# FPGA_DDR3_IO.net
KiCad netlist of a schematic drawn in Altium Designer
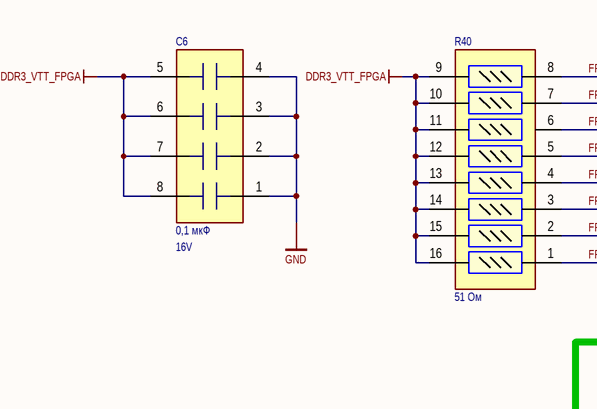
[diagram p0: FPGA_DDR3&IO.SchDoc, top left]
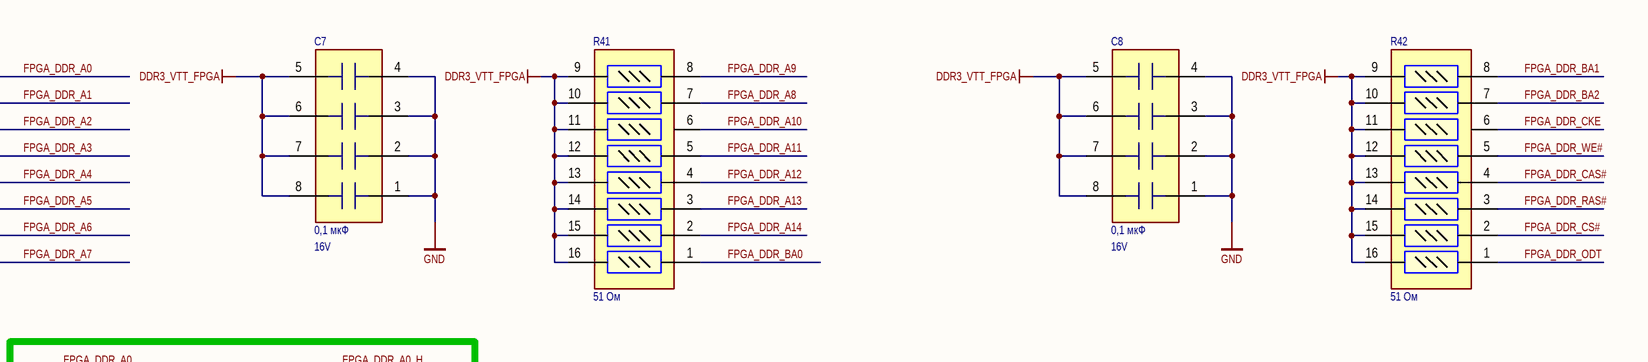
[diagram p1: FPGA_DDR3&IO.SchDoc, top right]
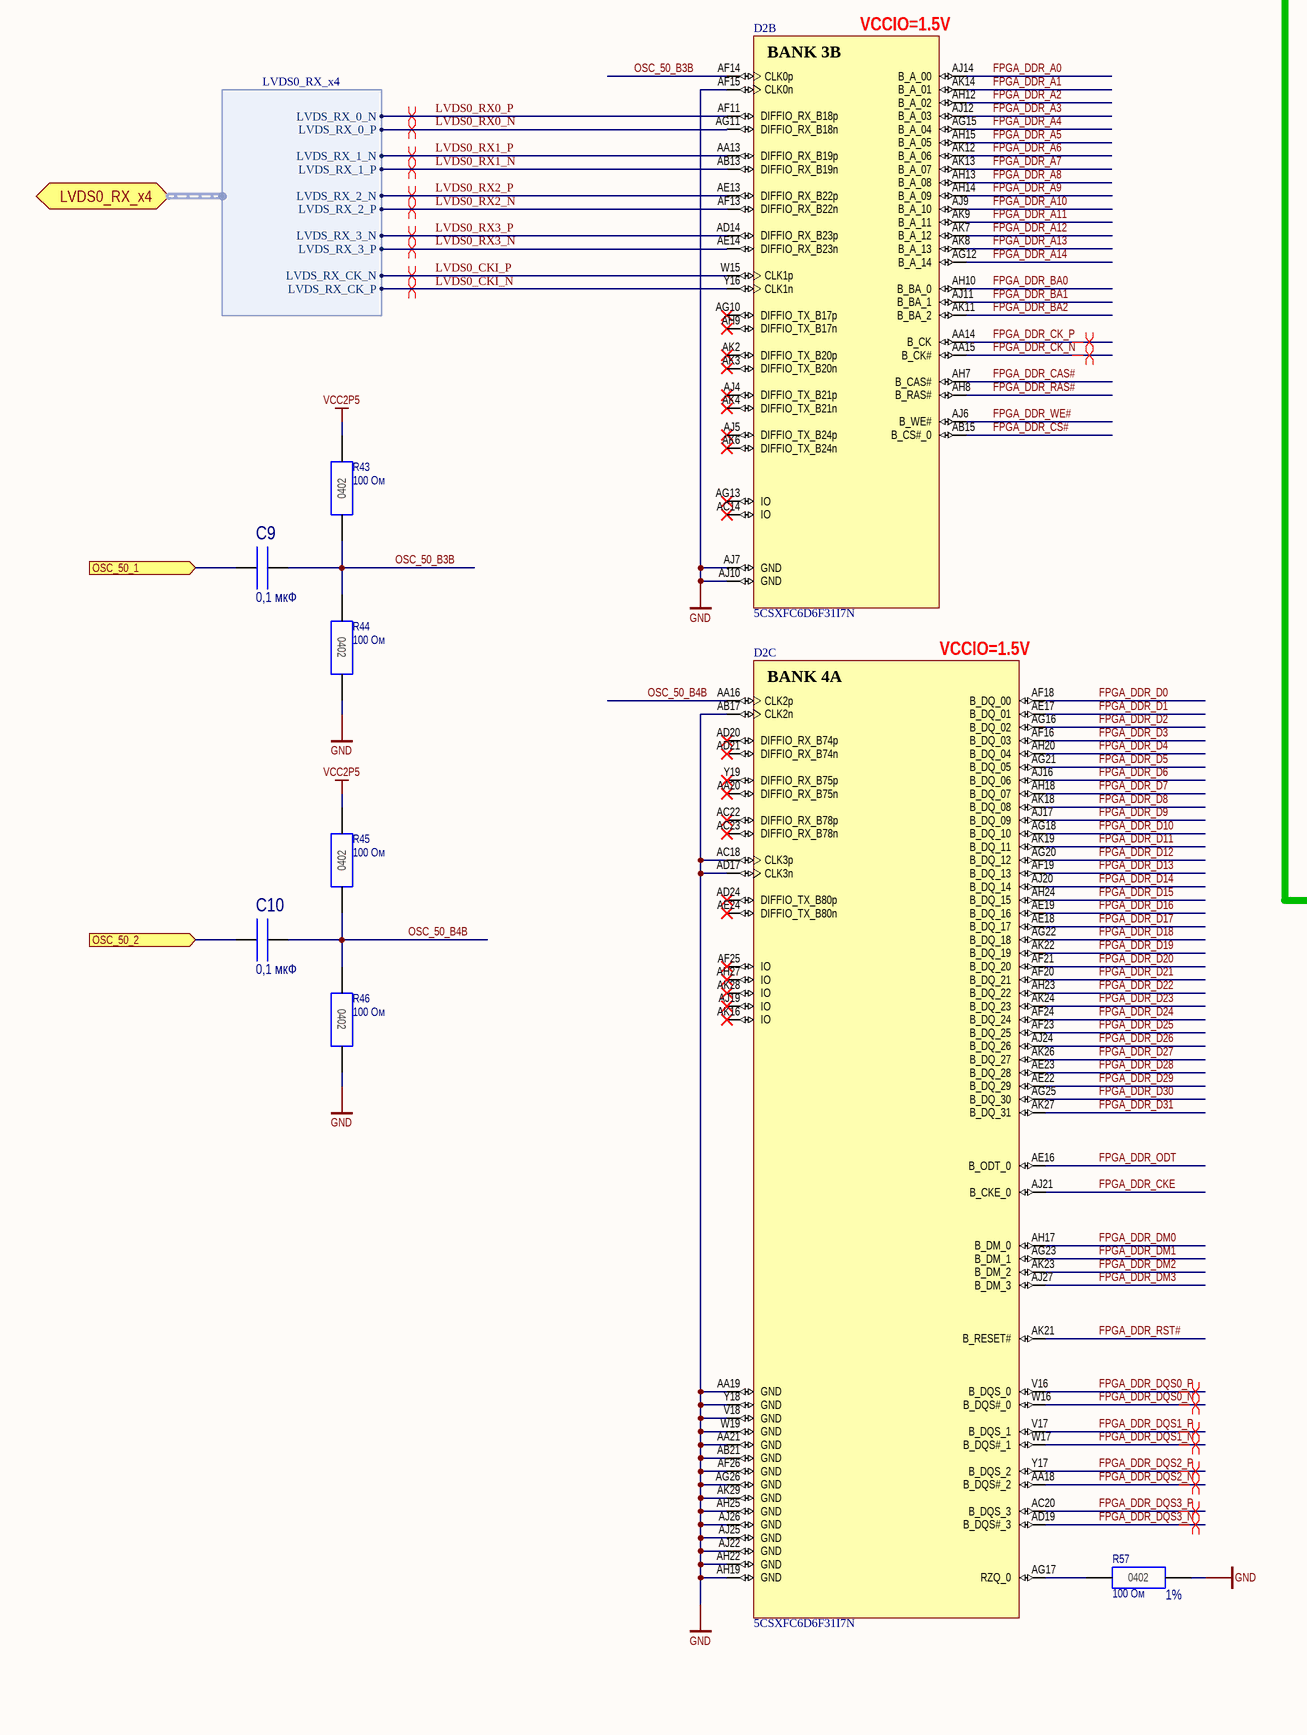
[diagram p2: FPGA_DDR3&IO.SchDoc, bottom left]
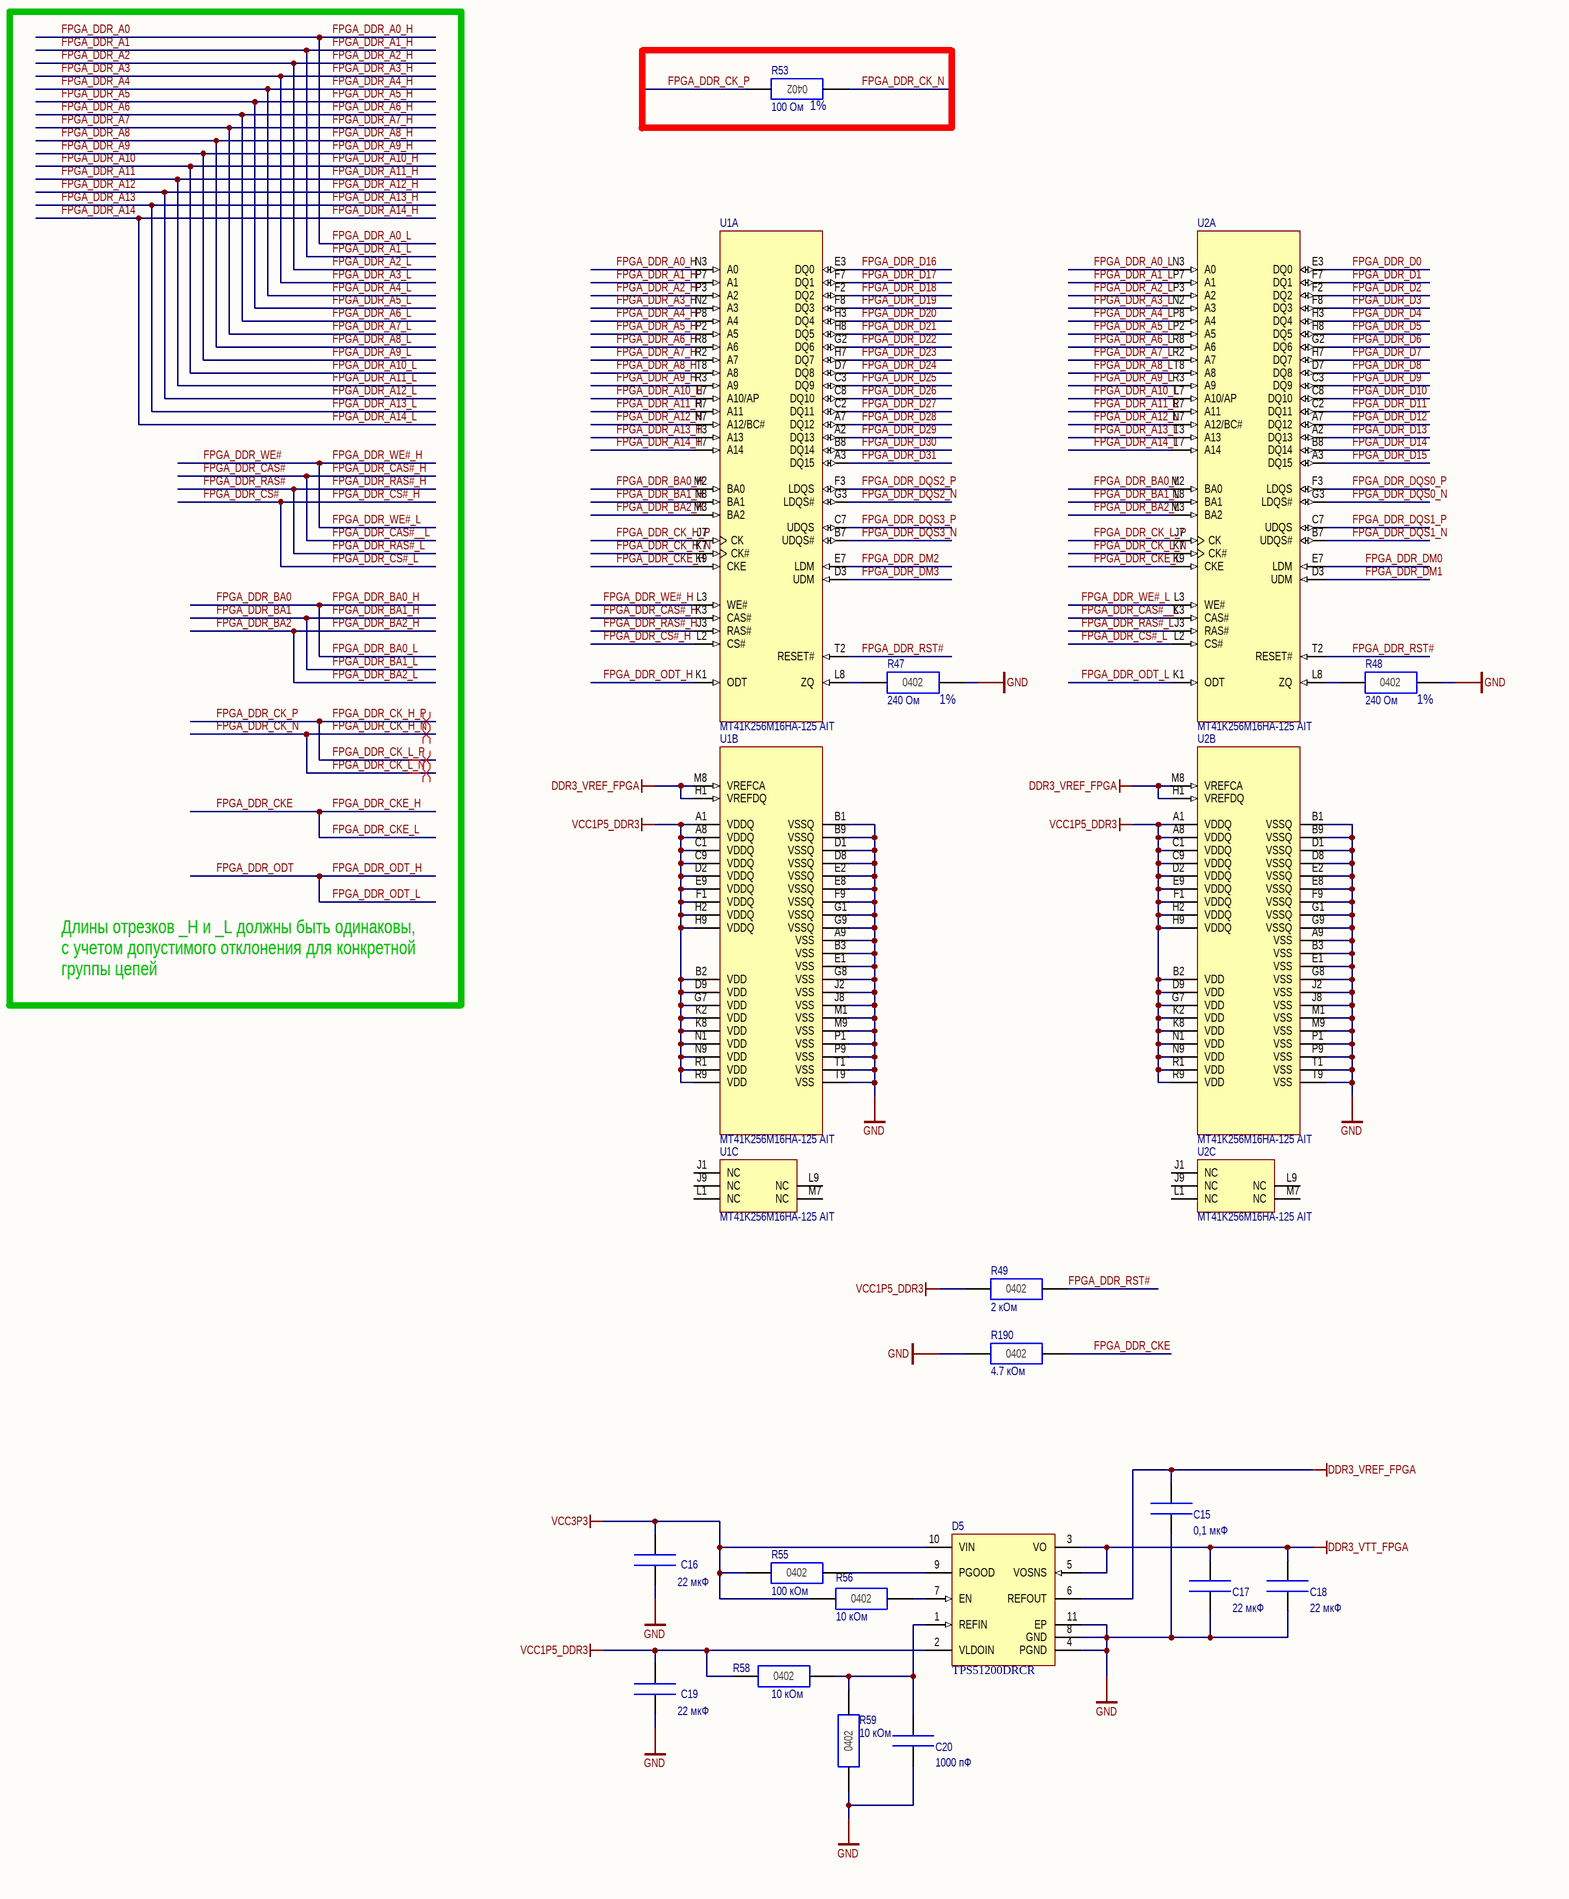
[diagram p3: FPGA_DDR3&IO.SchDoc, bottom right]

(export (version "E")
  (design (tool "Eeschema 10.0.6"))
  (components
    (comp (ref "C6")
      (value "0,1 мкФ")
      (footprint "CAF-80P319X159-8N")
      (description "Чип конденсатор керамический")
      (fields (field (name "V") "16V") (field (name "Comment") "W3A4YC104KAT2A"))
      (libsource (lib "SD_IC") (part "W3A4YC104KAT2A"))
    )
    (comp (ref "C7")
      (value "0,1 мкФ")
      (footprint "CAF-80P319X159-8N")
      (description "Чип конденсатор керамический")
      (fields (field (name "V") "16V") (field (name "Comment") "W3A4YC104KAT2A"))
      (libsource (lib "SD_IC") (part "W3A4YC104KAT2A"))
    )
    (comp (ref "C8")
      (value "0,1 мкФ")
      (footprint "CAF-80P319X159-8N")
      (description "Чип конденсатор керамический")
      (fields (field (name "V") "16V") (field (name "Comment") "W3A4YC104KAT2A"))
      (libsource (lib "SD_IC") (part "W3A4YC104KAT2A"))
    )
    (comp (ref "C9")
      (value "0,1 мкФ")
      (footprint "CC0402(1005)")
      (description "Чип конденсатор керамический")
      (fields (field (name "Comment") "CC0402-X7R-0,1 мкФ-20%-10В"))
      (libsource (lib "Чип конденсаторы") (part "CC0402-X7R-#-20%-10В"))
    )
    (comp (ref "C10")
      (value "0,1 мкФ")
      (footprint "CC0402(1005)")
      (description "Чип конденсатор керамический")
      (fields (field (name "Comment") "CC0402-X7R-0,1 мкФ-20%-10В"))
      (libsource (lib "Чип конденсаторы") (part "CC0402-X7R-#-20%-10В"))
    )
    (comp (ref "C15")
      (value "0,1 мкФ")
      (footprint "CC0402(1005)")
      (description "Чип конденсатор керамический")
      (fields (field (name "Comment") "CC0402-X7R-0,1 мкФ-20%-10В"))
      (libsource (lib "Чип конденсаторы") (part "CC0402-X7R-#-20%-10В"))
    )
    (comp (ref "C16")
      (value "22 мкФ")
      (footprint "CC0402(1005)")
      (description "Чип конденсатор керамический")
      (fields (field (name "Comment") "CC0402-X5R-22 мкФ-20%-6.3В"))
      (libsource (lib "Чип конденсаторы") (part "CC0402-X7R-#-20%-10В"))
    )
    (comp (ref "C17")
      (value "22 мкФ")
      (footprint "CC0402(1005)")
      (description "Чип конденсатор керамический")
      (fields (field (name "Comment") "CC0402-X5R-22 мкФ-20%-6.3В"))
      (libsource (lib "Чип конденсаторы") (part "CC0402-X7R-#-20%-10В"))
    )
    (comp (ref "C18")
      (value "22 мкФ")
      (footprint "CC0402(1005)")
      (description "Чип конденсатор керамический")
      (fields (field (name "Comment") "CC0402-X5R-22 мкФ-20%-6.3В"))
      (libsource (lib "Чип конденсаторы") (part "CC0402-X7R-#-20%-10В"))
    )
    (comp (ref "C19")
      (value "22 мкФ")
      (footprint "CC0402(1005)")
      (description "Чип конденсатор керамический")
      (fields (field (name "Comment") "CC0402-X5R-22 мкФ-20%-6.3В"))
      (libsource (lib "Чип конденсаторы") (part "CC0402-X7R-#-20%-10В"))
    )
    (comp (ref "C20")
      (value "1000 пФ")
      (footprint "CC0402(1005)")
      (description "Чип конденсатор керамический")
      (fields (field (name "Comment") "CC0402-NP01000 пФ-1%-50В"))
      (libsource (lib "Чип конденсаторы") (part "CC0402-X7R-#-20%-10В"))
    )
    (comp (ref "D2")
      (value "5CSXFC6D6F31I7N")
      (footprint "ALTR-FBGA896_A-200")
      (fields (field (name "MANUFACTURER") "Altera"))
      (libsource (lib "Altera Cyclone V_sd") (part "5CSXFC6D6F31I7N"))
    )
    (comp (ref "D5")
      (value "TPS51200DRCR")
      (footprint "TI-DRC10-2400X1650TP_V")
      (fields (field (name "MANUFACTURER") "Texas Instruments"))
      (libsource (lib "SD_IC") (part "TPS51200DRCR"))
    )
    (comp (ref "R40")
      (value "51 Ом")
      (footprint "CAT16-J8")
      (description "Набор чип резисторов")
      (fields (field (name "Comment") "YC248-JR-07-51 Ом"))
      (libsource (lib "SD_IC") (part "YC248-JR-07-#"))
    )
    (comp (ref "R41")
      (value "51 Ом")
      (footprint "CAT16-J8")
      (description "Набор чип резисторов")
      (fields (field (name "Comment") "YC248-JR-07-51 Ом"))
      (libsource (lib "SD_IC") (part "YC248-JR-07-#"))
    )
    (comp (ref "R42")
      (value "51 Ом")
      (footprint "CAT16-J8")
      (description "Набор чип резисторов")
      (fields (field (name "Comment") "YC248-JR-07-51 Ом"))
      (libsource (lib "SD_IC") (part "YC248-JR-07-#"))
    )
    (comp (ref "R43")
      (value "100 Ом")
      (footprint "CR0402(1005)")
      (description "Чип резистор")
      (fields (field (name "TOLERANCE") "5%") (field (name "Comment") "CR0402-100 Ом-±5%"))
      (libsource (lib "Резисторы") (part "CR0402-#-±5%"))
    )
    (comp (ref "R44")
      (value "100 Ом")
      (footprint "CR0402(1005)")
      (description "Чип резистор")
      (fields (field (name "TOLERANCE") "5%") (field (name "Comment") "CR0402-100 Ом-±5%"))
      (libsource (lib "") (part "CR0402-#-±5%_2"))
    )
    (comp (ref "R45")
      (value "100 Ом")
      (footprint "CR0402(1005)")
      (description "Чип резистор")
      (fields (field (name "TOLERANCE") "5%") (field (name "Comment") "CR0402-100 Ом-±5%"))
      (libsource (lib "Резисторы") (part "CR0402-#-±5%"))
    )
    (comp (ref "R46")
      (value "100 Ом")
      (footprint "CR0402(1005)")
      (description "Чип резистор")
      (fields (field (name "TOLERANCE") "5%") (field (name "Comment") "CR0402-100 Ом-±5%"))
      (libsource (lib "") (part "CR0402-#-±5%_2"))
    )
    (comp (ref "R47")
      (value "240 Ом")
      (footprint "CR0402(1005)")
      (description "Чип резистор")
      (fields (field (name "TOLERANCE") "1%") (field (name "Comment") "CR0402-240 Ом-±TOLERANCE"))
      (libsource (lib "") (part "CR0402-#-±5%_1"))
    )
    (comp (ref "R48")
      (value "240 Ом")
      (footprint "CR0402(1005)")
      (description "Чип резистор")
      (fields (field (name "TOLERANCE") "1%") (field (name "Comment") "CR0402-240 Ом-±TOLERANCE"))
      (libsource (lib "") (part "CR0402-#-±5%_1"))
    )
    (comp (ref "R49")
      (value "2 кОм")
      (footprint "CR0402(1005)")
      (description "Чип резистор")
      (fields (field (name "TOLERANCE") "5%") (field (name "Comment") "CR0402-2 кОм-±5%"))
      (libsource (lib "") (part "CR0402-#-±5%_1"))
    )
    (comp (ref "R53")
      (value "100 Ом")
      (footprint "CR0402(1005)")
      (description "Чип резистор")
      (fields (field (name "TOLERANCE") "1%") (field (name "Comment") "CR0402-100 Ом-±TOLERANCE"))
      (libsource (lib "") (part "CR0402-#-±5%_3"))
    )
    (comp (ref "R55")
      (value "100 кОм")
      (footprint "CR0402(1005)")
      (description "Чип резистор")
      (fields (field (name "TOLERANCE") "5%") (field (name "Comment") "CR0402-100 кОм-±5%"))
      (libsource (lib "") (part "CR0402-#-±5%_1"))
    )
    (comp (ref "R56")
      (value "10 кОм")
      (footprint "CR0402(1005)")
      (description "Чип резистор")
      (fields (field (name "TOLERANCE") "5%") (field (name "Comment") "CR0402-10 кОм-±5%"))
      (libsource (lib "") (part "CR0402-#-±5%_1"))
    )
    (comp (ref "R57")
      (value "100 Ом")
      (footprint "CR0402(1005)")
      (description "Чип резистор")
      (fields (field (name "TOLERANCE") "1%") (field (name "Comment") "CR0402-100 Ом-±TOLERANCE"))
      (libsource (lib "") (part "CR0402-#-±5%_1"))
    )
    (comp (ref "R58")
      (value "10 кОм")
      (footprint "CR0402(1005)")
      (description "Чип резистор")
      (fields (field (name "TOLERANCE") "5%") (field (name "Comment") "CR0402-10 кОм-±5%"))
      (libsource (lib "") (part "CR0402-#-±5%_1"))
    )
    (comp (ref "R59")
      (value "10 кОм")
      (footprint "CR0402(1005)")
      (description "Чип резистор")
      (fields (field (name "TOLERANCE") "5%") (field (name "Comment") "CR0402-10 кОм-±5%"))
      (libsource (lib "Резисторы") (part "CR0402-#-±5%"))
    )
    (comp (ref "R190")
      (value "4.7 кОм")
      (footprint "CR0402(1005)")
      (description "Чип резистор")
      (fields (field (name "TOLERANCE") "5%") (field (name "Comment") "CR0402-4.7 кОм-±5%"))
      (libsource (lib "") (part "CR0402-#-±5%_1"))
    )
    (comp (ref "U1")
      (value "MT41K256M16HA-125 AIT")
      (footprint "MICT-HA-96")
      (description "4Gb DDR3-1600 SDRAM, 256Mb x 16, 1.25ns, 1.35V, -40 to 95 degC, 96-Ball FBGA, Pb-Free")
      (fields (field (name "VOLTAGE") "1.35V ") (field (name "MANUFACTURER") "Micron"))
      (libsource (lib "SD_IC") (part "MT41K256M16HA-125 AIT"))
    )
    (comp (ref "U2")
      (value "MT41K256M16HA-125 AIT")
      (footprint "MICT-HA-96")
      (description "4Gb DDR3-1600 SDRAM, 256Mb x 16, 1.25ns, 1.35V, -40 to 95 degC, 96-Ball FBGA, Pb-Free")
      (fields (field (name "VOLTAGE") "1.35V ") (field (name "MANUFACTURER") "Micron"))
      (libsource (lib "SD_IC") (part "MT41K256M16HA-125 AIT"))
    )
  )
  (nets
    (net (code "2") (name "/FPGA_DDR_A0") (class "Default")
      (node (ref "D2") (pin "AJ14") (pinfunction "B_A_00_AJ14") (pintype "bidirectional"))
      (node (ref "R40") (pin "8") (pintype "passive"))
      (node (ref "U1") (pin "N3") (pinfunction "A0_N3") (pintype "input"))
      (node (ref "U2") (pin "N3") (pinfunction "A0_N3") (pintype "input"))
    )
    (net (code "3") (name "/FPGA_DDR_A1") (class "Default")
      (node (ref "D2") (pin "AK14") (pinfunction "B_A_01_AK14") (pintype "bidirectional"))
      (node (ref "R40") (pin "7") (pintype "passive"))
      (node (ref "U1") (pin "P7") (pinfunction "A1_P7") (pintype "input"))
      (node (ref "U2") (pin "P7") (pinfunction "A1_P7") (pintype "input"))
    )
    (net (code "4") (name "/FPGA_DDR_A2") (class "Default")
      (node (ref "D2") (pin "AH12") (pinfunction "B_A_02_AH12") (pintype "bidirectional"))
      (node (ref "R40") (pin "6") (pintype "passive"))
      (node (ref "U1") (pin "P3") (pinfunction "A2_P3") (pintype "input"))
      (node (ref "U2") (pin "P3") (pinfunction "A2_P3") (pintype "input"))
    )
    (net (code "5") (name "/FPGA_DDR_A3") (class "Default")
      (node (ref "D2") (pin "AJ12") (pinfunction "B_A_03_AJ12") (pintype "bidirectional"))
      (node (ref "R40") (pin "5") (pintype "passive"))
      (node (ref "U1") (pin "N2") (pinfunction "A3_N2") (pintype "input"))
      (node (ref "U2") (pin "N2") (pinfunction "A3_N2") (pintype "input"))
    )
    (net (code "6") (name "/FPGA_DDR_A4") (class "Default")
      (node (ref "D2") (pin "AG15") (pinfunction "B_A_04_AG15") (pintype "bidirectional"))
      (node (ref "R40") (pin "4") (pintype "passive"))
      (node (ref "U1") (pin "P8") (pinfunction "A4_P8") (pintype "input"))
      (node (ref "U2") (pin "P8") (pinfunction "A4_P8") (pintype "input"))
    )
    (net (code "7") (name "/FPGA_DDR_A5") (class "Default")
      (node (ref "D2") (pin "AH15") (pinfunction "B_A_05_AH15") (pintype "bidirectional"))
      (node (ref "R40") (pin "3") (pintype "passive"))
      (node (ref "U1") (pin "P2") (pinfunction "A5_P2") (pintype "input"))
      (node (ref "U2") (pin "P2") (pinfunction "A5_P2") (pintype "input"))
    )
    (net (code "8") (name "/FPGA_DDR_A6") (class "Default")
      (node (ref "D2") (pin "AK12") (pinfunction "B_A_06_AK12") (pintype "bidirectional"))
      (node (ref "R40") (pin "2") (pintype "passive"))
      (node (ref "U1") (pin "R8") (pinfunction "A6_R8") (pintype "input"))
      (node (ref "U2") (pin "R8") (pinfunction "A6_R8") (pintype "input"))
    )
    (net (code "9") (name "/FPGA_DDR_A7") (class "Default")
      (node (ref "D2") (pin "AK13") (pinfunction "B_A_07_AK13") (pintype "bidirectional"))
      (node (ref "R40") (pin "1") (pintype "passive"))
      (node (ref "U1") (pin "R2") (pinfunction "A7_R2") (pintype "input"))
      (node (ref "U2") (pin "R2") (pinfunction "A7_R2") (pintype "input"))
    )
    (net (code "10") (name "/FPGA_DDR_A8") (class "Default")
      (node (ref "D2") (pin "AH13") (pinfunction "B_A_08_AH13") (pintype "bidirectional"))
      (node (ref "R41") (pin "7") (pintype "passive"))
      (node (ref "U1") (pin "T8") (pinfunction "A8_T8") (pintype "input"))
      (node (ref "U2") (pin "T8") (pinfunction "A8_T8") (pintype "input"))
    )
    (net (code "11") (name "/FPGA_DDR_A9") (class "Default")
      (node (ref "D2") (pin "AH14") (pinfunction "B_A_09_AH14") (pintype "bidirectional"))
      (node (ref "R41") (pin "8") (pintype "passive"))
      (node (ref "U1") (pin "R3") (pinfunction "A9_R3") (pintype "input"))
      (node (ref "U2") (pin "R3") (pinfunction "A9_R3") (pintype "input"))
    )
    (net (code "12") (name "/FPGA_DDR_A10") (class "Default")
      (node (ref "D2") (pin "AJ9") (pinfunction "B_A_10_AJ9") (pintype "bidirectional"))
      (node (ref "R41") (pin "6") (pintype "passive"))
      (node (ref "U1") (pin "L7") (pinfunction "A10/AP_L7") (pintype "input"))
      (node (ref "U2") (pin "L7") (pinfunction "A10/AP_L7") (pintype "input"))
    )
    (net (code "13") (name "/FPGA_DDR_A11") (class "Default")
      (node (ref "D2") (pin "AK9") (pinfunction "B_A_11_AK9") (pintype "bidirectional"))
      (node (ref "R41") (pin "5") (pintype "passive"))
      (node (ref "U1") (pin "R7") (pinfunction "A11_R7") (pintype "input"))
      (node (ref "U2") (pin "R7") (pinfunction "A11_R7") (pintype "input"))
    )
    (net (code "14") (name "/FPGA_DDR_A12") (class "Default")
      (node (ref "D2") (pin "AK7") (pinfunction "B_A_12_AK7") (pintype "bidirectional"))
      (node (ref "R41") (pin "4") (pintype "passive"))
      (node (ref "U1") (pin "N7") (pinfunction "A12/BC#_N7") (pintype "input"))
      (node (ref "U2") (pin "N7") (pinfunction "A12/BC#_N7") (pintype "input"))
    )
    (net (code "15") (name "/FPGA_DDR_A13") (class "Default")
      (node (ref "D2") (pin "AK8") (pinfunction "B_A_13_AK8") (pintype "bidirectional"))
      (node (ref "R41") (pin "3") (pintype "passive"))
      (node (ref "U1") (pin "T3") (pinfunction "A13_T3") (pintype "input"))
      (node (ref "U2") (pin "T3") (pinfunction "A13_T3") (pintype "input"))
    )
    (net (code "16") (name "/FPGA_DDR_A14") (class "Default")
      (node (ref "D2") (pin "AG12") (pinfunction "B_A_14_AG12") (pintype "bidirectional"))
      (node (ref "R41") (pin "2") (pintype "passive"))
      (node (ref "U1") (pin "T7") (pinfunction "A14_T7") (pintype "input"))
      (node (ref "U2") (pin "T7") (pinfunction "A14_T7") (pintype "input"))
    )
    (net (code "17") (name "/FPGA_DDR_BA0") (class "Default")
      (node (ref "D2") (pin "AH10") (pinfunction "B_BA_0_AH10") (pintype "bidirectional"))
      (node (ref "R41") (pin "1") (pintype "passive"))
      (node (ref "U1") (pin "M2") (pinfunction "BA0_M2") (pintype "input"))
      (node (ref "U2") (pin "M2") (pinfunction "BA0_M2") (pintype "input"))
    )
    (net (code "18") (name "/FPGA_DDR_BA1") (class "Default")
      (node (ref "D2") (pin "AJ11") (pinfunction "B_BA_1_AJ11") (pintype "bidirectional"))
      (node (ref "R42") (pin "8") (pintype "passive"))
      (node (ref "U1") (pin "N8") (pinfunction "BA1_N8") (pintype "input"))
      (node (ref "U2") (pin "N8") (pinfunction "BA1_N8") (pintype "input"))
    )
    (net (code "19") (name "/FPGA_DDR_BA2") (class "Default")
      (node (ref "D2") (pin "AK11") (pinfunction "B_BA_2_AK11") (pintype "bidirectional"))
      (node (ref "R42") (pin "7") (pintype "passive"))
      (node (ref "U1") (pin "M3") (pinfunction "BA2_M3") (pintype "input"))
      (node (ref "U2") (pin "M3") (pinfunction "BA2_M3") (pintype "input"))
    )
    (net (code "20") (name "/FPGA_DDR_CAS#") (class "Default")
      (node (ref "D2") (pin "AH7") (pinfunction "B_CAS#_AH7") (pintype "bidirectional"))
      (node (ref "R42") (pin "4") (pintype "passive"))
      (node (ref "U1") (pin "K3") (pinfunction "CAS#_K3") (pintype "input"))
      (node (ref "U2") (pin "K3") (pinfunction "CAS#_K3") (pintype "input"))
    )
    (net (code "21") (name "/FPGA_DDR_CKE") (class "Default")
      (node (ref "D2") (pin "AJ21") (pinfunction "B_CKE_0_AJ21") (pintype "bidirectional"))
      (node (ref "R190") (pin "2") (pinfunction "-_2") (pintype "passive"))
      (node (ref "R42") (pin "6") (pintype "passive"))
      (node (ref "U1") (pin "K9") (pinfunction "CKE_K9") (pintype "input"))
      (node (ref "U2") (pin "K9") (pinfunction "CKE_K9") (pintype "input"))
    )
    (net (code "22") (name "/FPGA_DDR_CK_H_N") (class "Default")
      (node (ref "D2") (pin "AA15") (pinfunction "B_CK#_AA15") (pintype "bidirectional"))
      (node (ref "R53") (pin "1") (pinfunction "+_1") (pintype "passive"))
      (node (ref "U1") (pin "K7") (pinfunction "CK#_K7") (pintype "input"))
      (node (ref "U2") (pin "K7") (pinfunction "CK#_K7") (pintype "input"))
    )
    (net (code "23") (name "/FPGA_DDR_CK_H_P") (class "Default")
      (node (ref "D2") (pin "AA14") (pinfunction "B_CK_AA14") (pintype "bidirectional"))
      (node (ref "R53") (pin "2") (pinfunction "-_2") (pintype "passive"))
      (node (ref "U1") (pin "J7") (pinfunction "CK_J7") (pintype "input"))
      (node (ref "U2") (pin "J7") (pinfunction "CK_J7") (pintype "input"))
    )
    (net (code "24") (name "/FPGA_DDR_CS#") (class "Default")
      (node (ref "D2") (pin "AB15") (pinfunction "B_CS#_0_AB15") (pintype "bidirectional"))
      (node (ref "R42") (pin "2") (pintype "passive"))
      (node (ref "U1") (pin "L2") (pinfunction "CS#_L2") (pintype "input"))
      (node (ref "U2") (pin "L2") (pinfunction "CS#_L2") (pintype "input"))
    )
    (net (code "25") (name "/FPGA_DDR_D0") (class "Default")
      (node (ref "D2") (pin "AF18") (pinfunction "B_DQ_00_AF18") (pintype "bidirectional"))
      (node (ref "U2") (pin "E3") (pinfunction "DQ0_E3") (pintype "bidirectional"))
    )
    (net (code "26") (name "/FPGA_DDR_D1") (class "Default")
      (node (ref "D2") (pin "AE17") (pinfunction "B_DQ_01_AE17") (pintype "bidirectional"))
      (node (ref "U2") (pin "F7") (pinfunction "DQ1_F7") (pintype "bidirectional"))
    )
    (net (code "27") (name "/FPGA_DDR_D2") (class "Default")
      (node (ref "D2") (pin "AG16") (pinfunction "B_DQ_02_AG16") (pintype "bidirectional"))
      (node (ref "U2") (pin "F2") (pinfunction "DQ2_F2") (pintype "bidirectional"))
    )
    (net (code "28") (name "/FPGA_DDR_D3") (class "Default")
      (node (ref "D2") (pin "AF16") (pinfunction "B_DQ_03_AF16") (pintype "bidirectional"))
      (node (ref "U2") (pin "F8") (pinfunction "DQ3_F8") (pintype "bidirectional"))
    )
    (net (code "29") (name "/FPGA_DDR_D4") (class "Default")
      (node (ref "D2") (pin "AH20") (pinfunction "B_DQ_04_AH20") (pintype "bidirectional"))
      (node (ref "U2") (pin "H3") (pinfunction "DQ4_H3") (pintype "bidirectional"))
    )
    (net (code "30") (name "/FPGA_DDR_D5") (class "Default")
      (node (ref "D2") (pin "AG21") (pinfunction "B_DQ_05_AG21") (pintype "bidirectional"))
      (node (ref "U2") (pin "H8") (pinfunction "DQ5_H8") (pintype "bidirectional"))
    )
    (net (code "31") (name "/FPGA_DDR_D6") (class "Default")
      (node (ref "D2") (pin "AJ16") (pinfunction "B_DQ_06_AJ16") (pintype "bidirectional"))
      (node (ref "U2") (pin "G2") (pinfunction "DQ6_G2") (pintype "bidirectional"))
    )
    (net (code "32") (name "/FPGA_DDR_D7") (class "Default")
      (node (ref "D2") (pin "AH18") (pinfunction "B_DQ_07_AH18") (pintype "bidirectional"))
      (node (ref "U2") (pin "H7") (pinfunction "DQ7_H7") (pintype "bidirectional"))
    )
    (net (code "33") (name "/FPGA_DDR_D8") (class "Default")
      (node (ref "D2") (pin "AK18") (pinfunction "B_DQ_08_AK18") (pintype "bidirectional"))
      (node (ref "U2") (pin "D7") (pinfunction "DQ8_D7") (pintype "bidirectional"))
    )
    (net (code "34") (name "/FPGA_DDR_D9") (class "Default")
      (node (ref "D2") (pin "AJ17") (pinfunction "B_DQ_09_AJ17") (pintype "bidirectional"))
      (node (ref "U2") (pin "C3") (pinfunction "DQ9_C3") (pintype "bidirectional"))
    )
    (net (code "35") (name "/FPGA_DDR_D10") (class "Default")
      (node (ref "D2") (pin "AG18") (pinfunction "B_DQ_10_AG18") (pintype "bidirectional"))
      (node (ref "U2") (pin "C8") (pinfunction "DQ10_C8") (pintype "bidirectional"))
    )
    (net (code "36") (name "/FPGA_DDR_D11") (class "Default")
      (node (ref "D2") (pin "AK19") (pinfunction "B_DQ_11_AK19") (pintype "bidirectional"))
      (node (ref "U2") (pin "C2") (pinfunction "DQ11_C2") (pintype "bidirectional"))
    )
    (net (code "37") (name "/FPGA_DDR_D12") (class "Default")
      (node (ref "D2") (pin "AG20") (pinfunction "B_DQ_12_AG20") (pintype "bidirectional"))
      (node (ref "U2") (pin "A7") (pinfunction "DQ12_A7") (pintype "bidirectional"))
    )
    (net (code "38") (name "/FPGA_DDR_D13") (class "Default")
      (node (ref "D2") (pin "AF19") (pinfunction "B_DQ_13_AF19") (pintype "bidirectional"))
      (node (ref "U2") (pin "A2") (pinfunction "DQ13_A2") (pintype "bidirectional"))
    )
    (net (code "39") (name "/FPGA_DDR_D14") (class "Default")
      (node (ref "D2") (pin "AJ20") (pinfunction "B_DQ_14_AJ20") (pintype "bidirectional"))
      (node (ref "U2") (pin "B8") (pinfunction "DQ14_B8") (pintype "bidirectional"))
    )
    (net (code "40") (name "/FPGA_DDR_D15") (class "Default")
      (node (ref "D2") (pin "AH24") (pinfunction "B_DQ_15_AH24") (pintype "bidirectional"))
      (node (ref "U2") (pin "A3") (pinfunction "DQ15_A3") (pintype "bidirectional"))
    )
    (net (code "41") (name "/FPGA_DDR_D16") (class "Default")
      (node (ref "D2") (pin "AE19") (pinfunction "B_DQ_16_AE19") (pintype "bidirectional"))
      (node (ref "U1") (pin "E3") (pinfunction "DQ0_E3") (pintype "bidirectional"))
    )
    (net (code "42") (name "/FPGA_DDR_D17") (class "Default")
      (node (ref "D2") (pin "AE18") (pinfunction "B_DQ_17_AE18") (pintype "bidirectional"))
      (node (ref "U1") (pin "F7") (pinfunction "DQ1_F7") (pintype "bidirectional"))
    )
    (net (code "43") (name "/FPGA_DDR_D18") (class "Default")
      (node (ref "D2") (pin "AG22") (pinfunction "B_DQ_18_AG22") (pintype "bidirectional"))
      (node (ref "U1") (pin "F2") (pinfunction "DQ2_F2") (pintype "bidirectional"))
    )
    (net (code "44") (name "/FPGA_DDR_D19") (class "Default")
      (node (ref "D2") (pin "AK22") (pinfunction "B_DQ_19_AK22") (pintype "bidirectional"))
      (node (ref "U1") (pin "F8") (pinfunction "DQ3_F8") (pintype "bidirectional"))
    )
    (net (code "45") (name "/FPGA_DDR_D20") (class "Default")
      (node (ref "D2") (pin "AF21") (pinfunction "B_DQ_20_AF21") (pintype "bidirectional"))
      (node (ref "U1") (pin "H3") (pinfunction "DQ4_H3") (pintype "bidirectional"))
    )
    (net (code "46") (name "/FPGA_DDR_D21") (class "Default")
      (node (ref "D2") (pin "AF20") (pinfunction "B_DQ_21_AF20") (pintype "bidirectional"))
      (node (ref "U1") (pin "H8") (pinfunction "DQ5_H8") (pintype "bidirectional"))
    )
    (net (code "47") (name "/FPGA_DDR_D22") (class "Default")
      (node (ref "D2") (pin "AH23") (pinfunction "B_DQ_22_AH23") (pintype "bidirectional"))
      (node (ref "U1") (pin "G2") (pinfunction "DQ6_G2") (pintype "bidirectional"))
    )
    (net (code "48") (name "/FPGA_DDR_D23") (class "Default")
      (node (ref "D2") (pin "AK24") (pinfunction "B_DQ_23_AK24") (pintype "bidirectional"))
      (node (ref "U1") (pin "H7") (pinfunction "DQ7_H7") (pintype "bidirectional"))
    )
    (net (code "49") (name "/FPGA_DDR_D24") (class "Default")
      (node (ref "D2") (pin "AF24") (pinfunction "B_DQ_24_AF24") (pintype "bidirectional"))
      (node (ref "U1") (pin "D7") (pinfunction "DQ8_D7") (pintype "bidirectional"))
    )
    (net (code "50") (name "/FPGA_DDR_D25") (class "Default")
      (node (ref "D2") (pin "AF23") (pinfunction "B_DQ_25_AF23") (pintype "bidirectional"))
      (node (ref "U1") (pin "C3") (pinfunction "DQ9_C3") (pintype "bidirectional"))
    )
    (net (code "51") (name "/FPGA_DDR_D26") (class "Default")
      (node (ref "D2") (pin "AJ24") (pinfunction "B_DQ_26_AJ24") (pintype "bidirectional"))
      (node (ref "U1") (pin "C8") (pinfunction "DQ10_C8") (pintype "bidirectional"))
    )
    (net (code "52") (name "/FPGA_DDR_D27") (class "Default")
      (node (ref "D2") (pin "AK26") (pinfunction "B_DQ_27_AK26") (pintype "bidirectional"))
      (node (ref "U1") (pin "C2") (pinfunction "DQ11_C2") (pintype "bidirectional"))
    )
    (net (code "53") (name "/FPGA_DDR_D28") (class "Default")
      (node (ref "D2") (pin "AE23") (pinfunction "B_DQ_28_AE23") (pintype "bidirectional"))
      (node (ref "U1") (pin "A7") (pinfunction "DQ12_A7") (pintype "bidirectional"))
    )
    (net (code "54") (name "/FPGA_DDR_D29") (class "Default")
      (node (ref "D2") (pin "AE22") (pinfunction "B_DQ_29_AE22") (pintype "bidirectional"))
      (node (ref "U1") (pin "A2") (pinfunction "DQ13_A2") (pintype "bidirectional"))
    )
    (net (code "55") (name "/FPGA_DDR_D30") (class "Default")
      (node (ref "D2") (pin "AG25") (pinfunction "B_DQ_30_AG25") (pintype "bidirectional"))
      (node (ref "U1") (pin "B8") (pinfunction "DQ14_B8") (pintype "bidirectional"))
    )
    (net (code "56") (name "/FPGA_DDR_D31") (class "Default")
      (node (ref "D2") (pin "AK27") (pinfunction "B_DQ_31_AK27") (pintype "bidirectional"))
      (node (ref "U1") (pin "A3") (pinfunction "DQ15_A3") (pintype "bidirectional"))
    )
    (net (code "57") (name "/FPGA_DDR_DM0") (class "Default")
      (node (ref "D2") (pin "AH17") (pinfunction "B_DM_0_AH17") (pintype "bidirectional"))
      (node (ref "U2") (pin "E7") (pinfunction "LDM_E7") (pintype "input"))
    )
    (net (code "58") (name "/FPGA_DDR_DM1") (class "Default")
      (node (ref "D2") (pin "AG23") (pinfunction "B_DM_1_AG23") (pintype "bidirectional"))
      (node (ref "U2") (pin "D3") (pinfunction "UDM_D3") (pintype "input"))
    )
    (net (code "59") (name "/FPGA_DDR_DM2") (class "Default")
      (node (ref "D2") (pin "AK23") (pinfunction "B_DM_2_AK23") (pintype "bidirectional"))
      (node (ref "U1") (pin "E7") (pinfunction "LDM_E7") (pintype "input"))
    )
    (net (code "60") (name "/FPGA_DDR_DM3") (class "Default")
      (node (ref "D2") (pin "AJ27") (pinfunction "B_DM_3_AJ27") (pintype "bidirectional"))
      (node (ref "U1") (pin "D3") (pinfunction "UDM_D3") (pintype "input"))
    )
    (net (code "61") (name "/FPGA_DDR_DQS0_N") (class "Default")
      (node (ref "D2") (pin "W16") (pinfunction "B_DQS#_0_W16") (pintype "bidirectional"))
      (node (ref "U2") (pin "G3") (pinfunction "LDQS#_G3") (pintype "bidirectional"))
    )
    (net (code "62") (name "/FPGA_DDR_DQS0_P") (class "Default")
      (node (ref "D2") (pin "V16") (pinfunction "B_DQS_0_V16") (pintype "bidirectional"))
      (node (ref "U2") (pin "F3") (pinfunction "LDQS_F3") (pintype "bidirectional"))
    )
    (net (code "63") (name "/FPGA_DDR_DQS1_N") (class "Default")
      (node (ref "D2") (pin "W17") (pinfunction "B_DQS#_1_W17") (pintype "bidirectional"))
      (node (ref "U2") (pin "B7") (pinfunction "UDQS#_B7") (pintype "bidirectional"))
    )
    (net (code "64") (name "/FPGA_DDR_DQS1_P") (class "Default")
      (node (ref "D2") (pin "V17") (pinfunction "B_DQS_1_V17") (pintype "bidirectional"))
      (node (ref "U2") (pin "C7") (pinfunction "UDQS_C7") (pintype "bidirectional"))
    )
    (net (code "65") (name "/FPGA_DDR_DQS2_N") (class "Default")
      (node (ref "D2") (pin "AA18") (pinfunction "B_DQS#_2_AA18") (pintype "bidirectional"))
      (node (ref "U1") (pin "G3") (pinfunction "LDQS#_G3") (pintype "bidirectional"))
    )
    (net (code "66") (name "/FPGA_DDR_DQS2_P") (class "Default")
      (node (ref "D2") (pin "Y17") (pinfunction "B_DQS_2_Y17") (pintype "bidirectional"))
      (node (ref "U1") (pin "F3") (pinfunction "LDQS_F3") (pintype "bidirectional"))
    )
    (net (code "67") (name "/FPGA_DDR_DQS3_N") (class "Default")
      (node (ref "D2") (pin "AD19") (pinfunction "B_DQS#_3_AD19") (pintype "bidirectional"))
      (node (ref "U1") (pin "B7") (pinfunction "UDQS#_B7") (pintype "bidirectional"))
    )
    (net (code "68") (name "/FPGA_DDR_DQS3_P") (class "Default")
      (node (ref "D2") (pin "AC20") (pinfunction "B_DQS_3_AC20") (pintype "bidirectional"))
      (node (ref "U1") (pin "C7") (pinfunction "UDQS_C7") (pintype "bidirectional"))
    )
    (net (code "69") (name "/FPGA_DDR_ODT") (class "Default")
      (node (ref "D2") (pin "AE16") (pinfunction "B_ODT_0_AE16") (pintype "bidirectional"))
      (node (ref "R42") (pin "1") (pintype "passive"))
      (node (ref "U1") (pin "K1") (pinfunction "ODT_K1") (pintype "input"))
      (node (ref "U2") (pin "K1") (pinfunction "ODT_K1") (pintype "input"))
    )
    (net (code "70") (name "/FPGA_DDR_RAS#") (class "Default")
      (node (ref "D2") (pin "AH8") (pinfunction "B_RAS#_AH8") (pintype "bidirectional"))
      (node (ref "R42") (pin "3") (pintype "passive"))
      (node (ref "U1") (pin "J3") (pinfunction "RAS#_J3") (pintype "input"))
      (node (ref "U2") (pin "J3") (pinfunction "RAS#_J3") (pintype "input"))
    )
    (net (code "71") (name "/FPGA_DDR_RST#") (class "Default")
      (node (ref "D2") (pin "AK21") (pinfunction "B_RESET#_AK21") (pintype "bidirectional"))
      (node (ref "R49") (pin "2") (pinfunction "-_2") (pintype "passive"))
      (node (ref "U1") (pin "T2") (pinfunction "RESET#_T2") (pintype "input"))
      (node (ref "U2") (pin "T2") (pinfunction "RESET#_T2") (pintype "input"))
    )
    (net (code "72") (name "/FPGA_DDR_WE#") (class "Default")
      (node (ref "D2") (pin "AJ6") (pinfunction "B_WE#_AJ6") (pintype "bidirectional"))
      (node (ref "R42") (pin "5") (pintype "passive"))
      (node (ref "U1") (pin "L3") (pinfunction "WE#_L3") (pintype "input"))
      (node (ref "U2") (pin "L3") (pinfunction "WE#_L3") (pintype "input"))
    )
    (net (code "74") (name "/LVDS0_CKI_P") (class "Default")
      (node (ref "D2") (pin "W15") (pinfunction "CLK1p_W15") (pintype "bidirectional"))
    )
    (net (code "76") (name "/LVDS0_RX0_P") (class "Default")
      (node (ref "D2") (pin "AF11") (pinfunction "DIFFIO_RX_B18p_AF11") (pintype "bidirectional"))
    )
    (net (code "77") (name "/LVDS0_RX1_N") (class "Default")
      (node (ref "D2") (pin "AB13") (pinfunction "DIFFIO_RX_B19n_AB13") (pintype "bidirectional"))
    )
    (net (code "78") (name "/LVDS0_RX1_P") (class "Default")
      (node (ref "D2") (pin "AA13") (pinfunction "DIFFIO_RX_B19p_AA13") (pintype "bidirectional"))
    )
    (net (code "79") (name "/LVDS0_RX2_N") (class "Default")
      (node (ref "D2") (pin "AF13") (pinfunction "DIFFIO_RX_B22n_AF13") (pintype "bidirectional"))
    )
    (net (code "80") (name "/LVDS0_RX2_P") (class "Default")
      (node (ref "D2") (pin "AE13") (pinfunction "DIFFIO_RX_B22p_AE13") (pintype "bidirectional"))
    )
    (net (code "82") (name "/LVDS0_RX3_N") (class "Default")
      (node (ref "D2") (pin "AE14") (pinfunction "DIFFIO_RX_B23n_AE14") (pintype "bidirectional"))
    )
    (net (code "83") (name "/LVDS0_RX3_P") (class "Default")
      (node (ref "D2") (pin "AD14") (pinfunction "DIFFIO_RX_B23p_AD14") (pintype "bidirectional"))
    )
    (net (code "84") (name "/OSC_50_1") (class "Default")
      (node (ref "C9") (pin "1") (pinfunction "+_1") (pintype "passive"))
    )
    (net (code "85") (name "/OSC_50_2") (class "Default")
      (node (ref "C10") (pin "1") (pinfunction "+_1") (pintype "passive"))
    )
    (net (code "86") (name "/OSC_50_B3B") (class "Default")
      (node (ref "C9") (pin "2") (pinfunction "-_2") (pintype "passive"))
      (node (ref "D2") (pin "AF14") (pinfunction "CLK0p_AF14") (pintype "bidirectional"))
      (node (ref "R43") (pin "1") (pinfunction "+_1") (pintype "passive"))
      (node (ref "R44") (pin "1") (pinfunction "+_1") (pintype "passive"))
    )
    (net (code "88") (name "/OSC_50_B4B") (class "Default")
      (node (ref "C10") (pin "2") (pinfunction "-_2") (pintype "passive"))
      (node (ref "D2") (pin "AA16") (pinfunction "CLK2p_AA16") (pintype "bidirectional"))
      (node (ref "R45") (pin "1") (pinfunction "+_1") (pintype "passive"))
      (node (ref "R46") (pin "1") (pinfunction "+_1") (pintype "passive"))
    )
    (net (code "89") (name "DDR3_VREF_FPGA") (class "Default")
      (node (ref "C15") (pin "1") (pinfunction "+_1") (pintype "passive"))
      (node (ref "D5") (pin "6") (pinfunction "REFOUT_6") (pintype "power_in"))
      (node (ref "U1") (pin "H1") (pinfunction "VREFDQ_H1") (pintype "input"))
      (node (ref "U1") (pin "M8") (pinfunction "VREFCA_M8") (pintype "input"))
      (node (ref "U2") (pin "H1") (pinfunction "VREFDQ_H1") (pintype "input"))
      (node (ref "U2") (pin "M8") (pinfunction "VREFCA_M8") (pintype "input"))
    )
    (net (code "90") (name "DDR3_VTT_FPGA") (class "Default")
      (node (ref "C17") (pin "1") (pinfunction "+_1") (pintype "passive"))
      (node (ref "C18") (pin "1") (pinfunction "+_1") (pintype "passive"))
      (node (ref "C6") (pin "5") (pintype "passive"))
      (node (ref "C6") (pin "6") (pintype "passive"))
      (node (ref "C6") (pin "7") (pintype "passive"))
      (node (ref "C6") (pin "8") (pintype "passive"))
      (node (ref "C7") (pin "5") (pintype "passive"))
      (node (ref "C7") (pin "6") (pintype "passive"))
      (node (ref "C7") (pin "7") (pintype "passive"))
      (node (ref "C7") (pin "8") (pintype "passive"))
      (node (ref "C8") (pin "5") (pintype "passive"))
      (node (ref "C8") (pin "6") (pintype "passive"))
      (node (ref "C8") (pin "7") (pintype "passive"))
      (node (ref "C8") (pin "8") (pintype "passive"))
      (node (ref "D5") (pin "3") (pinfunction "VO_3") (pintype "power_in"))
      (node (ref "D5") (pin "5") (pinfunction "VOSNS_5") (pintype "input"))
      (node (ref "R40") (pin "10") (pintype "passive"))
      (node (ref "R40") (pin "11") (pintype "passive"))
      (node (ref "R40") (pin "12") (pintype "passive"))
      (node (ref "R40") (pin "13") (pintype "passive"))
      (node (ref "R40") (pin "14") (pintype "passive"))
      (node (ref "R40") (pin "15") (pintype "passive"))
      (node (ref "R40") (pin "16") (pintype "passive"))
      (node (ref "R40") (pin "9") (pintype "passive"))
      (node (ref "R41") (pin "10") (pintype "passive"))
      (node (ref "R41") (pin "11") (pintype "passive"))
      (node (ref "R41") (pin "12") (pintype "passive"))
      (node (ref "R41") (pin "13") (pintype "passive"))
      (node (ref "R41") (pin "14") (pintype "passive"))
      (node (ref "R41") (pin "15") (pintype "passive"))
      (node (ref "R41") (pin "16") (pintype "passive"))
      (node (ref "R41") (pin "9") (pintype "passive"))
      (node (ref "R42") (pin "10") (pintype "passive"))
      (node (ref "R42") (pin "11") (pintype "passive"))
      (node (ref "R42") (pin "12") (pintype "passive"))
      (node (ref "R42") (pin "13") (pintype "passive"))
      (node (ref "R42") (pin "14") (pintype "passive"))
      (node (ref "R42") (pin "15") (pintype "passive"))
      (node (ref "R42") (pin "16") (pintype "passive"))
      (node (ref "R42") (pin "9") (pintype "passive"))
    )
    (net (code "91") (name "GND") (class "Default")
      (node (ref "C15") (pin "2") (pinfunction "-_2") (pintype "passive"))
      (node (ref "C16") (pin "2") (pinfunction "-_2") (pintype "passive"))
      (node (ref "C17") (pin "2") (pinfunction "-_2") (pintype "passive"))
      (node (ref "C18") (pin "2") (pinfunction "-_2") (pintype "passive"))
      (node (ref "C19") (pin "2") (pinfunction "-_2") (pintype "passive"))
      (node (ref "C20") (pin "2") (pinfunction "-_2") (pintype "passive"))
      (node (ref "C6") (pin "1") (pintype "passive"))
      (node (ref "C6") (pin "2") (pintype "passive"))
      (node (ref "C6") (pin "3") (pintype "passive"))
      (node (ref "C6") (pin "4") (pintype "passive"))
      (node (ref "C7") (pin "1") (pintype "passive"))
      (node (ref "C7") (pin "2") (pintype "passive"))
      (node (ref "C7") (pin "3") (pintype "passive"))
      (node (ref "C7") (pin "4") (pintype "passive"))
      (node (ref "C8") (pin "1") (pintype "passive"))
      (node (ref "C8") (pin "2") (pintype "passive"))
      (node (ref "C8") (pin "3") (pintype "passive"))
      (node (ref "C8") (pin "4") (pintype "passive"))
      (node (ref "D2") (pin "AF15") (pinfunction "CLK0n_AF15") (pintype "bidirectional"))
      (node (ref "D2") (pin "AJ10") (pinfunction "GND_AJ10") (pintype "bidirectional"))
      (node (ref "D2") (pin "AJ22") (pinfunction "GND_AJ22") (pintype "bidirectional"))
      (node (ref "D2") (pin "AJ7") (pinfunction "GND_AJ7") (pintype "bidirectional"))
      (node (ref "D5") (pin "11") (pinfunction "EP_11") (pintype "power_in"))
      (node (ref "D5") (pin "4") (pinfunction "PGND_4") (pintype "power_in"))
      (node (ref "D5") (pin "8") (pinfunction "GND_8") (pintype "power_in"))
      (node (ref "R190") (pin "1") (pinfunction "+_1") (pintype "passive"))
      (node (ref "R44") (pin "2") (pinfunction "-_2") (pintype "passive"))
      (node (ref "R46") (pin "2") (pinfunction "-_2") (pintype "passive"))
      (node (ref "R47") (pin "2") (pinfunction "-_2") (pintype "passive"))
      (node (ref "R48") (pin "2") (pinfunction "-_2") (pintype "passive"))
      (node (ref "R57") (pin "2") (pinfunction "-_2") (pintype "passive"))
      (node (ref "R59") (pin "1") (pinfunction "+_1") (pintype "passive"))
      (node (ref "U1") (pin "A9") (pinfunction "VSS_A9") (pintype "power_in"))
      (node (ref "U1") (pin "B1") (pinfunction "VSSQ_B1") (pintype "power_in"))
      (node (ref "U1") (pin "B3") (pinfunction "VSS_B3") (pintype "power_in"))
      (node (ref "U1") (pin "B9") (pinfunction "VSSQ_B9") (pintype "power_in"))
      (node (ref "U1") (pin "D1") (pinfunction "VSSQ_D1") (pintype "power_in"))
      (node (ref "U1") (pin "D8") (pinfunction "VSSQ_D8") (pintype "power_in"))
      (node (ref "U1") (pin "E1") (pinfunction "VSS_E1") (pintype "power_in"))
      (node (ref "U1") (pin "E2") (pinfunction "VSSQ_E2") (pintype "power_in"))
      (node (ref "U1") (pin "E8") (pinfunction "VSSQ_E8") (pintype "power_in"))
      (node (ref "U1") (pin "F9") (pinfunction "VSSQ_F9") (pintype "power_in"))
      (node (ref "U1") (pin "G1") (pinfunction "VSSQ_G1") (pintype "power_in"))
      (node (ref "U1") (pin "G8") (pinfunction "VSS_G8") (pintype "power_in"))
      (node (ref "U1") (pin "G9") (pinfunction "VSSQ_G9") (pintype "power_in"))
      (node (ref "U1") (pin "J2") (pinfunction "VSS_J2") (pintype "power_in"))
      (node (ref "U1") (pin "J8") (pinfunction "VSS_J8") (pintype "power_in"))
      (node (ref "U1") (pin "M1") (pinfunction "VSS_M1") (pintype "power_in"))
      (node (ref "U1") (pin "M9") (pinfunction "VSS_M9") (pintype "power_in"))
      (node (ref "U1") (pin "P1") (pinfunction "VSS_P1") (pintype "power_in"))
      (node (ref "U1") (pin "P9") (pinfunction "VSS_P9") (pintype "power_in"))
      (node (ref "U1") (pin "T1") (pinfunction "VSS_T1") (pintype "power_in"))
      (node (ref "U1") (pin "T9") (pinfunction "VSS_T9") (pintype "power_in"))
      (node (ref "U2") (pin "A9") (pinfunction "VSS_A9") (pintype "power_in"))
      (node (ref "U2") (pin "B1") (pinfunction "VSSQ_B1") (pintype "power_in"))
      (node (ref "U2") (pin "B3") (pinfunction "VSS_B3") (pintype "power_in"))
      (node (ref "U2") (pin "B9") (pinfunction "VSSQ_B9") (pintype "power_in"))
      (node (ref "U2") (pin "D1") (pinfunction "VSSQ_D1") (pintype "power_in"))
      (node (ref "U2") (pin "D8") (pinfunction "VSSQ_D8") (pintype "power_in"))
      (node (ref "U2") (pin "E1") (pinfunction "VSS_E1") (pintype "power_in"))
      (node (ref "U2") (pin "E2") (pinfunction "VSSQ_E2") (pintype "power_in"))
      (node (ref "U2") (pin "E8") (pinfunction "VSSQ_E8") (pintype "power_in"))
      (node (ref "U2") (pin "F9") (pinfunction "VSSQ_F9") (pintype "power_in"))
      (node (ref "U2") (pin "G1") (pinfunction "VSSQ_G1") (pintype "power_in"))
      (node (ref "U2") (pin "G8") (pinfunction "VSS_G8") (pintype "power_in"))
      (node (ref "U2") (pin "G9") (pinfunction "VSSQ_G9") (pintype "power_in"))
      (node (ref "U2") (pin "J2") (pinfunction "VSS_J2") (pintype "power_in"))
      (node (ref "U2") (pin "J8") (pinfunction "VSS_J8") (pintype "power_in"))
      (node (ref "U2") (pin "M1") (pinfunction "VSS_M1") (pintype "power_in"))
      (node (ref "U2") (pin "M9") (pinfunction "VSS_M9") (pintype "power_in"))
      (node (ref "U2") (pin "P1") (pinfunction "VSS_P1") (pintype "power_in"))
      (node (ref "U2") (pin "P9") (pinfunction "VSS_P9") (pintype "power_in"))
      (node (ref "U2") (pin "T1") (pinfunction "VSS_T1") (pintype "power_in"))
      (node (ref "U2") (pin "T9") (pinfunction "VSS_T9") (pintype "power_in"))
    )
    (net (code "92") (name "Net-(C20-+)") (class "Default")
      (node (ref "C20") (pin "1") (pinfunction "+_1") (pintype "passive"))
      (node (ref "D5") (pin "1") (pinfunction "REFIN_1") (pintype "input"))
      (node (ref "R58") (pin "2") (pinfunction "-_2") (pintype "passive"))
      (node (ref "R59") (pin "2") (pinfunction "-_2") (pintype "passive"))
    )
    (net (code "93") (name "Net-(D2C-RZQ_0)") (class "Default")
      (node (ref "D2") (pin "AG17") (pinfunction "RZQ_0_AG17") (pintype "bidirectional"))
      (node (ref "R57") (pin "1") (pinfunction "+_1") (pintype "passive"))
    )
    (net (code "94") (name "Net-(D5-EN)") (class "Default")
      (node (ref "D5") (pin "7") (pinfunction "EN_7") (pintype "input"))
      (node (ref "R56") (pin "2") (pinfunction "-_2") (pintype "passive"))
    )
    (net (code "95") (name "Net-(D5-PGOOD)") (class "Default")
      (node (ref "D5") (pin "9") (pinfunction "PGOOD_9") (pintype "open_collector"))
      (node (ref "R55") (pin "2") (pinfunction "-_2") (pintype "passive"))
    )
    (net (code "96") (name "Net-(R47-+)") (class "Default")
      (node (ref "R47") (pin "1") (pinfunction "+_1") (pintype "passive"))
      (node (ref "U1") (pin "L8") (pinfunction "ZQ_L8") (pintype "input"))
    )
    (net (code "97") (name "Net-(R48-+)") (class "Default")
      (node (ref "R48") (pin "1") (pinfunction "+_1") (pintype "passive"))
      (node (ref "U2") (pin "L8") (pinfunction "ZQ_L8") (pintype "input"))
    )
    (net (code "98") (name "VCC1P5_DDR3") (class "Default")
      (node (ref "C19") (pin "1") (pinfunction "+_1") (pintype "passive"))
      (node (ref "D5") (pin "2") (pinfunction "VLDOIN_2") (pintype "power_in"))
      (node (ref "R49") (pin "1") (pinfunction "+_1") (pintype "passive"))
      (node (ref "R58") (pin "1") (pinfunction "+_1") (pintype "passive"))
      (node (ref "U1") (pin "A1") (pinfunction "VDDQ_A1") (pintype "power_in"))
      (node (ref "U1") (pin "A8") (pinfunction "VDDQ_A8") (pintype "power_in"))
      (node (ref "U1") (pin "B2") (pinfunction "VDD_B2") (pintype "power_in"))
      (node (ref "U1") (pin "C1") (pinfunction "VDDQ_C1") (pintype "power_in"))
      (node (ref "U1") (pin "C9") (pinfunction "VDDQ_C9") (pintype "power_in"))
      (node (ref "U1") (pin "D2") (pinfunction "VDDQ_D2") (pintype "power_in"))
      (node (ref "U1") (pin "D9") (pinfunction "VDD_D9") (pintype "power_in"))
      (node (ref "U1") (pin "E9") (pinfunction "VDDQ_E9") (pintype "power_in"))
      (node (ref "U1") (pin "F1") (pinfunction "VDDQ_F1") (pintype "power_in"))
      (node (ref "U1") (pin "G7") (pinfunction "VDD_G7") (pintype "power_in"))
      (node (ref "U1") (pin "H2") (pinfunction "VDDQ_H2") (pintype "power_in"))
      (node (ref "U1") (pin "H9") (pinfunction "VDDQ_H9") (pintype "power_in"))
      (node (ref "U1") (pin "K2") (pinfunction "VDD_K2") (pintype "power_in"))
      (node (ref "U1") (pin "K8") (pinfunction "VDD_K8") (pintype "power_in"))
      (node (ref "U1") (pin "N1") (pinfunction "VDD_N1") (pintype "power_in"))
      (node (ref "U1") (pin "N9") (pinfunction "VDD_N9") (pintype "power_in"))
      (node (ref "U1") (pin "R1") (pinfunction "VDD_R1") (pintype "power_in"))
      (node (ref "U1") (pin "R9") (pinfunction "VDD_R9") (pintype "power_in"))
      (node (ref "U2") (pin "A1") (pinfunction "VDDQ_A1") (pintype "power_in"))
      (node (ref "U2") (pin "A8") (pinfunction "VDDQ_A8") (pintype "power_in"))
      (node (ref "U2") (pin "B2") (pinfunction "VDD_B2") (pintype "power_in"))
      (node (ref "U2") (pin "C1") (pinfunction "VDDQ_C1") (pintype "power_in"))
      (node (ref "U2") (pin "C9") (pinfunction "VDDQ_C9") (pintype "power_in"))
      (node (ref "U2") (pin "D2") (pinfunction "VDDQ_D2") (pintype "power_in"))
      (node (ref "U2") (pin "D9") (pinfunction "VDD_D9") (pintype "power_in"))
      (node (ref "U2") (pin "E9") (pinfunction "VDDQ_E9") (pintype "power_in"))
      (node (ref "U2") (pin "F1") (pinfunction "VDDQ_F1") (pintype "power_in"))
      (node (ref "U2") (pin "G7") (pinfunction "VDD_G7") (pintype "power_in"))
      (node (ref "U2") (pin "H2") (pinfunction "VDDQ_H2") (pintype "power_in"))
      (node (ref "U2") (pin "H9") (pinfunction "VDDQ_H9") (pintype "power_in"))
      (node (ref "U2") (pin "K2") (pinfunction "VDD_K2") (pintype "power_in"))
      (node (ref "U2") (pin "K8") (pinfunction "VDD_K8") (pintype "power_in"))
      (node (ref "U2") (pin "N1") (pinfunction "VDD_N1") (pintype "power_in"))
      (node (ref "U2") (pin "N9") (pinfunction "VDD_N9") (pintype "power_in"))
      (node (ref "U2") (pin "R1") (pinfunction "VDD_R1") (pintype "power_in"))
      (node (ref "U2") (pin "R9") (pinfunction "VDD_R9") (pintype "power_in"))
    )
    (net (code "99") (name "VCC2P5") (class "Default")
      (node (ref "R43") (pin "2") (pinfunction "-_2") (pintype "passive"))
      (node (ref "R45") (pin "2") (pinfunction "-_2") (pintype "passive"))
    )
    (net (code "100") (name "VCC3P3") (class "Default")
      (node (ref "C16") (pin "1") (pinfunction "+_1") (pintype "passive"))
      (node (ref "D5") (pin "10") (pinfunction "VIN_10") (pintype "power_in"))
      (node (ref "R55") (pin "1") (pinfunction "+_1") (pintype "passive"))
      (node (ref "R56") (pin "1") (pinfunction "+_1") (pintype "passive"))
    )
    (net (code "101") (name "unconnected-(D2B-CLK1n-PadY16)") (class "Default")
      (node (ref "D2") (pin "Y16") (pinfunction "CLK1n_Y16") (pintype "bidirectional"))
    )
    (net (code "102") (name "unconnected-(D2B-DIFFIO_RX_B18n-PadAG11)") (class "Default")
      (node (ref "D2") (pin "AG11") (pinfunction "DIFFIO_RX_B18n_AG11") (pintype "bidirectional"))
    )
    (net (code "103") (name "unconnected-(D2B-DIFFIO_TX_B17n-PadAH9)") (class "Default")
      (node (ref "D2") (pin "AH9") (pinfunction "DIFFIO_TX_B17n_AH9") (pintype "bidirectional+no_connect"))
    )
    (net (code "104") (name "unconnected-(D2B-DIFFIO_TX_B17p-PadAG10)") (class "Default")
      (node (ref "D2") (pin "AG10") (pinfunction "DIFFIO_TX_B17p_AG10") (pintype "bidirectional+no_connect"))
    )
    (net (code "105") (name "unconnected-(D2B-DIFFIO_TX_B20n-PadAK3)") (class "Default")
      (node (ref "D2") (pin "AK3") (pinfunction "DIFFIO_TX_B20n_AK3") (pintype "bidirectional+no_connect"))
    )
    (net (code "106") (name "unconnected-(D2B-DIFFIO_TX_B20p-PadAK2)") (class "Default")
      (node (ref "D2") (pin "AK2") (pinfunction "DIFFIO_TX_B20p_AK2") (pintype "bidirectional+no_connect"))
    )
    (net (code "107") (name "unconnected-(D2B-DIFFIO_TX_B21n-PadAK4)") (class "Default")
      (node (ref "D2") (pin "AK4") (pinfunction "DIFFIO_TX_B21n_AK4") (pintype "bidirectional+no_connect"))
    )
    (net (code "108") (name "unconnected-(D2B-DIFFIO_TX_B21p-PadAJ4)") (class "Default")
      (node (ref "D2") (pin "AJ4") (pinfunction "DIFFIO_TX_B21p_AJ4") (pintype "bidirectional+no_connect"))
    )
    (net (code "109") (name "unconnected-(D2B-DIFFIO_TX_B24n-PadAK6)") (class "Default")
      (node (ref "D2") (pin "AK6") (pinfunction "DIFFIO_TX_B24n_AK6") (pintype "bidirectional+no_connect"))
    )
    (net (code "110") (name "unconnected-(D2B-DIFFIO_TX_B24p-PadAJ5)") (class "Default")
      (node (ref "D2") (pin "AJ5") (pinfunction "DIFFIO_TX_B24p_AJ5") (pintype "bidirectional+no_connect"))
    )
    (net (code "111") (name "unconnected-(D2B-IO-PadAC14)") (class "Default")
      (node (ref "D2") (pin "AC14") (pinfunction "IO_AC14") (pintype "bidirectional+no_connect"))
    )
    (net (code "112") (name "unconnected-(D2B-IO-PadAG13)") (class "Default")
      (node (ref "D2") (pin "AG13") (pinfunction "IO_AG13") (pintype "bidirectional+no_connect"))
    )
    (net (code "113") (name "unconnected-(D2C-CLK2n-PadAB17)") (class "Default")
      (node (ref "D2") (pin "AB17") (pinfunction "CLK2n_AB17") (pintype "bidirectional"))
    )
    (net (code "114") (name "unconnected-(D2C-CLK3n-PadAD17)") (class "Default")
      (node (ref "D2") (pin "AD17") (pinfunction "CLK3n_AD17") (pintype "bidirectional"))
    )
    (net (code "115") (name "unconnected-(D2C-CLK3p-PadAC18)") (class "Default")
      (node (ref "D2") (pin "AC18") (pinfunction "CLK3p_AC18") (pintype "bidirectional"))
    )
    (net (code "116") (name "unconnected-(D2C-DIFFIO_RX_B74n-PadAD21)") (class "Default")
      (node (ref "D2") (pin "AD21") (pinfunction "DIFFIO_RX_B74n_AD21") (pintype "bidirectional+no_connect"))
    )
    (net (code "117") (name "unconnected-(D2C-DIFFIO_RX_B74p-PadAD20)") (class "Default")
      (node (ref "D2") (pin "AD20") (pinfunction "DIFFIO_RX_B74p_AD20") (pintype "bidirectional+no_connect"))
    )
    (net (code "118") (name "unconnected-(D2C-DIFFIO_RX_B75n-PadAA20)") (class "Default")
      (node (ref "D2") (pin "AA20") (pinfunction "DIFFIO_RX_B75n_AA20") (pintype "bidirectional+no_connect"))
    )
    (net (code "119") (name "unconnected-(D2C-DIFFIO_RX_B75p-PadY19)") (class "Default")
      (node (ref "D2") (pin "Y19") (pinfunction "DIFFIO_RX_B75p_Y19") (pintype "bidirectional+no_connect"))
    )
    (net (code "120") (name "unconnected-(D2C-DIFFIO_RX_B78n-PadAC23)") (class "Default")
      (node (ref "D2") (pin "AC23") (pinfunction "DIFFIO_RX_B78n_AC23") (pintype "bidirectional+no_connect"))
    )
    (net (code "121") (name "unconnected-(D2C-DIFFIO_RX_B78p-PadAC22)") (class "Default")
      (node (ref "D2") (pin "AC22") (pinfunction "DIFFIO_RX_B78p_AC22") (pintype "bidirectional+no_connect"))
    )
    (net (code "122") (name "unconnected-(D2C-DIFFIO_TX_B80n-PadAE24)") (class "Default")
      (node (ref "D2") (pin "AE24") (pinfunction "DIFFIO_TX_B80n_AE24") (pintype "bidirectional+no_connect"))
    )
    (net (code "123") (name "unconnected-(D2C-DIFFIO_TX_B80p-PadAD24)") (class "Default")
      (node (ref "D2") (pin "AD24") (pinfunction "DIFFIO_TX_B80p_AD24") (pintype "bidirectional+no_connect"))
    )
    (net (code "124") (name "unconnected-(D2C-GND-PadAA19)") (class "Default")
      (node (ref "D2") (pin "AA19") (pinfunction "GND_AA19") (pintype "bidirectional"))
    )
    (net (code "125") (name "unconnected-(D2C-GND-PadAA21)") (class "Default")
      (node (ref "D2") (pin "AA21") (pinfunction "GND_AA21") (pintype "bidirectional"))
    )
    (net (code "126") (name "unconnected-(D2C-GND-PadAB21)") (class "Default")
      (node (ref "D2") (pin "AB21") (pinfunction "GND_AB21") (pintype "bidirectional"))
    )
    (net (code "127") (name "unconnected-(D2C-GND-PadAF26)") (class "Default")
      (node (ref "D2") (pin "AF26") (pinfunction "GND_AF26") (pintype "bidirectional"))
    )
    (net (code "128") (name "unconnected-(D2C-GND-PadAG26)") (class "Default")
      (node (ref "D2") (pin "AG26") (pinfunction "GND_AG26") (pintype "bidirectional"))
    )
    (net (code "129") (name "unconnected-(D2C-GND-PadAH19)") (class "Default")
      (node (ref "D2") (pin "AH19") (pinfunction "GND_AH19") (pintype "bidirectional"))
    )
    (net (code "130") (name "unconnected-(D2C-GND-PadAH22)") (class "Default")
      (node (ref "D2") (pin "AH22") (pinfunction "GND_AH22") (pintype "bidirectional"))
    )
    (net (code "131") (name "unconnected-(D2C-GND-PadAH25)") (class "Default")
      (node (ref "D2") (pin "AH25") (pinfunction "GND_AH25") (pintype "bidirectional"))
    )
    (net (code "132") (name "unconnected-(D2C-GND-PadAJ25)") (class "Default")
      (node (ref "D2") (pin "AJ25") (pinfunction "GND_AJ25") (pintype "bidirectional"))
    )
    (net (code "133") (name "unconnected-(D2C-GND-PadAJ26)") (class "Default")
      (node (ref "D2") (pin "AJ26") (pinfunction "GND_AJ26") (pintype "bidirectional"))
    )
    (net (code "134") (name "unconnected-(D2C-GND-PadAK29)") (class "Default")
      (node (ref "D2") (pin "AK29") (pinfunction "GND_AK29") (pintype "bidirectional"))
    )
    (net (code "135") (name "unconnected-(D2C-GND-PadV18)") (class "Default")
      (node (ref "D2") (pin "V18") (pinfunction "GND_V18") (pintype "bidirectional"))
    )
    (net (code "136") (name "unconnected-(D2C-GND-PadW19)") (class "Default")
      (node (ref "D2") (pin "W19") (pinfunction "GND_W19") (pintype "bidirectional"))
    )
    (net (code "137") (name "unconnected-(D2C-GND-PadY18)") (class "Default")
      (node (ref "D2") (pin "Y18") (pinfunction "GND_Y18") (pintype "bidirectional"))
    )
    (net (code "138") (name "unconnected-(D2C-IO-PadAF25)") (class "Default")
      (node (ref "D2") (pin "AF25") (pinfunction "IO_AF25") (pintype "bidirectional+no_connect"))
    )
    (net (code "139") (name "unconnected-(D2C-IO-PadAH27)") (class "Default")
      (node (ref "D2") (pin "AH27") (pinfunction "IO_AH27") (pintype "bidirectional+no_connect"))
    )
    (net (code "140") (name "unconnected-(D2C-IO-PadAJ19)") (class "Default")
      (node (ref "D2") (pin "AJ19") (pinfunction "IO_AJ19") (pintype "bidirectional+no_connect"))
    )
    (net (code "141") (name "unconnected-(D2C-IO-PadAK16)") (class "Default")
      (node (ref "D2") (pin "AK16") (pinfunction "IO_AK16") (pintype "bidirectional+no_connect"))
    )
    (net (code "142") (name "unconnected-(D2C-IO-PadAK28)") (class "Default")
      (node (ref "D2") (pin "AK28") (pinfunction "IO_AK28") (pintype "bidirectional+no_connect"))
    )
    (net (code "143") (name "unconnected-(U1C-NC-PadJ1)") (class "Default")
      (node (ref "U1") (pin "J1") (pinfunction "NC_J1") (pintype "passive"))
    )
    (net (code "144") (name "unconnected-(U1C-NC-PadJ9)") (class "Default")
      (node (ref "U1") (pin "J9") (pinfunction "NC_J9") (pintype "passive"))
    )
    (net (code "145") (name "unconnected-(U1C-NC-PadL1)") (class "Default")
      (node (ref "U1") (pin "L1") (pinfunction "NC_L1") (pintype "passive"))
    )
    (net (code "146") (name "unconnected-(U1C-NC-PadL9)") (class "Default")
      (node (ref "U1") (pin "L9") (pinfunction "NC_L9") (pintype "passive"))
    )
    (net (code "147") (name "unconnected-(U1C-NC-PadM7)") (class "Default")
      (node (ref "U1") (pin "M7") (pinfunction "NC_M7") (pintype "passive"))
    )
    (net (code "148") (name "unconnected-(U2C-NC-PadJ1)") (class "Default")
      (node (ref "U2") (pin "J1") (pinfunction "NC_J1") (pintype "passive"))
    )
    (net (code "149") (name "unconnected-(U2C-NC-PadJ9)") (class "Default")
      (node (ref "U2") (pin "J9") (pinfunction "NC_J9") (pintype "passive"))
    )
    (net (code "150") (name "unconnected-(U2C-NC-PadL1)") (class "Default")
      (node (ref "U2") (pin "L1") (pinfunction "NC_L1") (pintype "passive"))
    )
    (net (code "151") (name "unconnected-(U2C-NC-PadL9)") (class "Default")
      (node (ref "U2") (pin "L9") (pinfunction "NC_L9") (pintype "passive"))
    )
    (net (code "152") (name "unconnected-(U2C-NC-PadM7)") (class "Default")
      (node (ref "U2") (pin "M7") (pinfunction "NC_M7") (pintype "passive"))
    )
  )
)
